# Interface.net
KiCad netlist of a schematic drawn in EAGLE
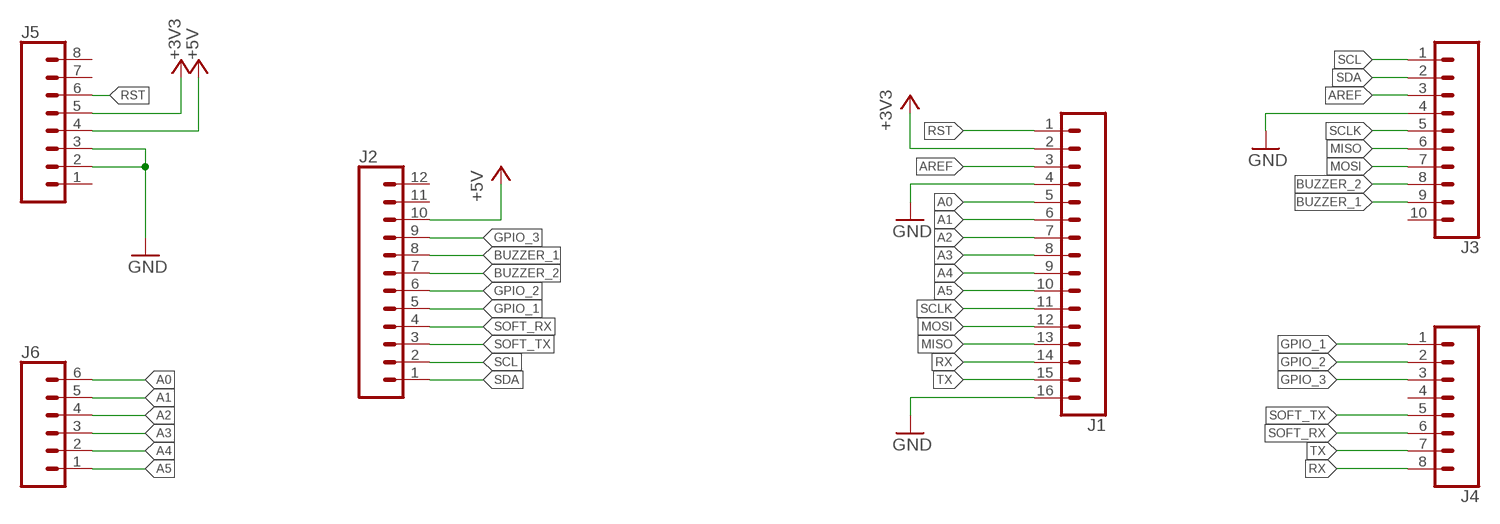
[diagram p0: schematic, sheet 1]

(export (version "E")
  (design (tool "Eeschema 10.0.6"))
  (components
    (comp (ref "J1")
      (value "CONN_16")
      (footprint "eagle-import:1X16")
      (libsource (lib "eagle-import") (part "CONN_16"))
    )
    (comp (ref "J2")
      (value "CONN_12")
      (footprint "eagle-import:1X12")
      (libsource (lib "eagle-import") (part "CONN_12"))
    )
    (comp (ref "J3")
      (value "CONN_10\"")
      (footprint "eagle-import:1X10")
      (libsource (lib "eagle-import") (part "CONN_10{dblquote}"))
    )
    (comp (ref "J4")
      (value "CONN_08\"")
      (footprint "eagle-import:1X08")
      (libsource (lib "eagle-import") (part "CONN_08{dblquote}"))
    )
    (comp (ref "J5")
      (value "CONN_08\"")
      (footprint "eagle-import:1X08")
      (libsource (lib "eagle-import") (part "CONN_08{dblquote}"))
    )
    (comp (ref "J6")
      (value "CONN_06SILK_FEMALE_PTH")
      (footprint "eagle-import:1X06")
      (libsource (lib "eagle-import") (part "CONN_06SILK_FEMALE_PTH"))
    )
  )
  (nets
    (net (code "1") (name "+3V3") (class "Default")
      (node (ref "J1") (pin "2") (pinfunction "2_2") (pintype "passive"))
      (node (ref "J5") (pin "5") (pinfunction "5_5") (pintype "passive"))
    )
    (net (code "2") (name "+5V") (class "Default")
      (node (ref "J2") (pin "10") (pinfunction "10_10") (pintype "passive"))
      (node (ref "J5") (pin "4") (pinfunction "4_4") (pintype "passive"))
    )
    (net (code "3") (name "A0") (class "Default")
      (node (ref "J1") (pin "5") (pinfunction "5_5") (pintype "passive"))
      (node (ref "J6") (pin "6") (pinfunction "6_6") (pintype "passive"))
    )
    (net (code "4") (name "A1") (class "Default")
      (node (ref "J1") (pin "6") (pinfunction "6_6") (pintype "passive"))
      (node (ref "J6") (pin "5") (pinfunction "5_5") (pintype "passive"))
    )
    (net (code "5") (name "A2") (class "Default")
      (node (ref "J1") (pin "7") (pinfunction "7_7") (pintype "passive"))
      (node (ref "J6") (pin "4") (pinfunction "4_4") (pintype "passive"))
    )
    (net (code "6") (name "A3") (class "Default")
      (node (ref "J1") (pin "8") (pinfunction "8_8") (pintype "passive"))
      (node (ref "J6") (pin "3") (pinfunction "3_3") (pintype "passive"))
    )
    (net (code "7") (name "A4") (class "Default")
      (node (ref "J1") (pin "9") (pinfunction "9_9") (pintype "passive"))
      (node (ref "J6") (pin "2") (pinfunction "2_2") (pintype "passive"))
    )
    (net (code "8") (name "A5") (class "Default")
      (node (ref "J1") (pin "10") (pinfunction "10_10") (pintype "passive"))
      (node (ref "J6") (pin "1") (pinfunction "1_1") (pintype "passive"))
    )
    (net (code "9") (name "AREF") (class "Default")
      (node (ref "J1") (pin "3") (pinfunction "3_3") (pintype "passive"))
      (node (ref "J3") (pin "3") (pinfunction "3_3") (pintype "passive"))
    )
    (net (code "10") (name "BUZZER_1") (class "Default")
      (node (ref "J2") (pin "8") (pinfunction "8_8") (pintype "passive"))
      (node (ref "J3") (pin "9") (pinfunction "9_9") (pintype "passive"))
    )
    (net (code "11") (name "BUZZER_2") (class "Default")
      (node (ref "J2") (pin "7") (pinfunction "7_7") (pintype "passive"))
      (node (ref "J3") (pin "8") (pinfunction "8_8") (pintype "passive"))
    )
    (net (code "12") (name "GND") (class "Default")
      (node (ref "J1") (pin "16") (pinfunction "16_16") (pintype "passive"))
      (node (ref "J1") (pin "4") (pinfunction "4_4") (pintype "passive"))
      (node (ref "J3") (pin "4") (pinfunction "4_4") (pintype "passive"))
      (node (ref "J5") (pin "2") (pinfunction "2_2") (pintype "passive"))
      (node (ref "J5") (pin "3") (pinfunction "3_3") (pintype "passive"))
    )
    (net (code "13") (name "GPIO_1") (class "Default")
      (node (ref "J2") (pin "5") (pinfunction "5_5") (pintype "passive"))
      (node (ref "J4") (pin "1") (pinfunction "1_1") (pintype "passive"))
    )
    (net (code "14") (name "GPIO_2") (class "Default")
      (node (ref "J2") (pin "6") (pinfunction "6_6") (pintype "passive"))
      (node (ref "J4") (pin "2") (pinfunction "2_2") (pintype "passive"))
    )
    (net (code "15") (name "GPIO_3") (class "Default")
      (node (ref "J2") (pin "9") (pinfunction "9_9") (pintype "passive"))
      (node (ref "J4") (pin "3") (pinfunction "3_3") (pintype "passive"))
    )
    (net (code "16") (name "MISO") (class "Default")
      (node (ref "J1") (pin "13") (pinfunction "13_13") (pintype "passive"))
      (node (ref "J3") (pin "6") (pinfunction "6_6") (pintype "passive"))
    )
    (net (code "17") (name "MOSI") (class "Default")
      (node (ref "J1") (pin "12") (pinfunction "12_12") (pintype "passive"))
      (node (ref "J3") (pin "7") (pinfunction "7_7") (pintype "passive"))
    )
    (net (code "18") (name "RST") (class "Default")
      (node (ref "J1") (pin "1") (pinfunction "1_1") (pintype "passive"))
      (node (ref "J5") (pin "6") (pinfunction "6_6") (pintype "passive"))
    )
    (net (code "19") (name "RX") (class "Default")
      (node (ref "J1") (pin "14") (pinfunction "14_14") (pintype "passive"))
      (node (ref "J4") (pin "8") (pinfunction "8_8") (pintype "passive"))
    )
    (net (code "20") (name "SCL") (class "Default")
      (node (ref "J2") (pin "2") (pinfunction "2_2") (pintype "passive"))
      (node (ref "J3") (pin "1") (pinfunction "1_1") (pintype "passive"))
    )
    (net (code "21") (name "SCLK") (class "Default")
      (node (ref "J1") (pin "11") (pinfunction "11_11") (pintype "passive"))
      (node (ref "J3") (pin "5") (pinfunction "5_5") (pintype "passive"))
    )
    (net (code "22") (name "SDA") (class "Default")
      (node (ref "J2") (pin "1") (pinfunction "1_1") (pintype "passive"))
      (node (ref "J3") (pin "2") (pinfunction "2_2") (pintype "passive"))
    )
    (net (code "23") (name "SOFT_RX") (class "Default")
      (node (ref "J2") (pin "4") (pinfunction "4_4") (pintype "passive"))
      (node (ref "J4") (pin "6") (pinfunction "6_6") (pintype "passive"))
    )
    (net (code "24") (name "SOFT_TX") (class "Default")
      (node (ref "J2") (pin "3") (pinfunction "3_3") (pintype "passive"))
      (node (ref "J4") (pin "5") (pinfunction "5_5") (pintype "passive"))
    )
    (net (code "25") (name "TX") (class "Default")
      (node (ref "J1") (pin "15") (pinfunction "15_15") (pintype "passive"))
      (node (ref "J4") (pin "7") (pinfunction "7_7") (pintype "passive"))
    )
    (net (code "26") (name "unconnected-(J2-Pad11)") (class "Default")
      (node (ref "J2") (pin "11") (pinfunction "11_11") (pintype "passive"))
    )
    (net (code "27") (name "unconnected-(J2-Pad12)") (class "Default")
      (node (ref "J2") (pin "12") (pinfunction "12_12") (pintype "passive"))
    )
    (net (code "28") (name "unconnected-(J3-Pad10)") (class "Default")
      (node (ref "J3") (pin "10") (pinfunction "10_10") (pintype "passive"))
    )
    (net (code "29") (name "unconnected-(J4-Pad4)") (class "Default")
      (node (ref "J4") (pin "4") (pinfunction "4_4") (pintype "passive"))
    )
    (net (code "30") (name "unconnected-(J5-Pad1)") (class "Default")
      (node (ref "J5") (pin "1") (pinfunction "1_1") (pintype "passive"))
    )
    (net (code "31") (name "unconnected-(J5-Pad7)") (class "Default")
      (node (ref "J5") (pin "7") (pinfunction "7_7") (pintype "passive"))
    )
    (net (code "32") (name "unconnected-(J5-Pad8)") (class "Default")
      (node (ref "J5") (pin "8") (pinfunction "8_8") (pintype "passive"))
    )
  )
)
